# lm2731.net
KiCad netlist of a schematic drawn in Altium Designer
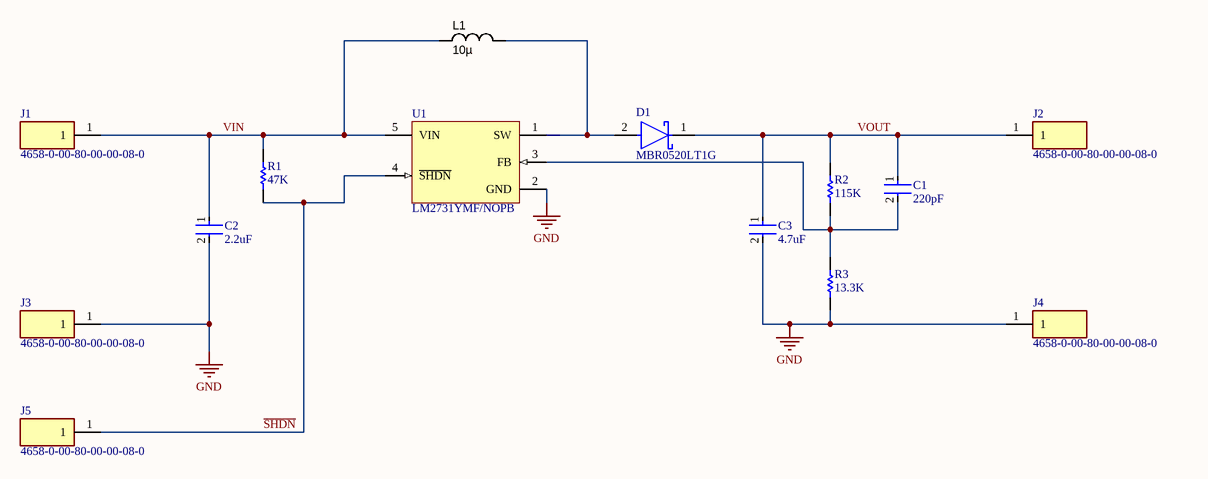
[diagram p0: lm2731.SchDoc]

(export (version "E")
  (design (tool "Eeschema 10.0.6"))
  (components
    (comp (ref "C1")
      (value "220pF")
      (footprint "FP-CL10-IPC_C")
      (description "Cap Ceramic 220pF 50V C0G ±5% Pad SMD 0603 +125°C T/R")
      (fields (field (name "VOLTAGE") "50V") (field (name "TOLERANCE") "5%"))
      (libsource (lib "Altium Content Vault") (part "b4654b650e69147ec39a6b967a45e02"))
    )
    (comp (ref "C2")
      (value "2.2uF")
      (footprint "FP-GRM188-0_2-IPC_C")
      (description "Chip Multilayer Ceramic Capacitors for General Purpose, 0603, 2.2uF, X5R, 15%, 10%, 50V")
      (fields (field (name "TOLERANCE") "10%"))
      (libsource (lib "Altium Content Vault") (part "11868f565c42a9108669ba33697ecf6"))
    )
    (comp (ref "C3")
      (value "4.7uF")
      (footprint "FP-GRM31C-0_2-e0_3_0_8-IPC_C")
      (description "Chip Multilayer Ceramic Capacitors for General Purpose, 1206, 4.7uF, X7R, 15%, 10%, 50V")
      (fields (field (name "VOLTAGE") "50V") (field (name "TOLERANCE") "10%"))
      (libsource (lib "Altium Content Vault") (part "02cd4be3c70576c341d710602a673aa"))
    )
    (comp (ref "D1")
      (value "MBR0520LT1G")
      (footprint "FP-425-04-IPC_C")
      (description "DIODE SCHOTTKY 20V 500MA SOD123")
      (libsource (lib "Altium Content Vault") (part "1d6ec82d83fb6aee721767c19dac4b9"))
    )
    (comp (ref "J1")
      (value "4658-0-00-80-00-00-08-0")
      (footprint "SamacSys:4658000800000080")
      (description "Connector")
      (fields (field (name "MOUSER PART NUMBER") "575-4658000800000080"))
      (libsource (lib "SamacSys") (part "4658-0-00-80-00-00-08-0"))
    )
    (comp (ref "J2")
      (value "4658-0-00-80-00-00-08-0")
      (footprint "4658000800000080")
      (description "Connector")
      (fields (field (name "MOUSER PART NUMBER") "575-4658000800000080"))
      (libsource (lib "") (part "4658-0-00-80-00-00-08-0_1"))
    )
    (comp (ref "J3")
      (value "4658-0-00-80-00-00-08-0")
      (footprint "4658000800000080")
      (description "Connector")
      (fields (field (name "MOUSER PART NUMBER") "575-4658000800000080"))
      (libsource (lib "SamacSys") (part "4658-0-00-80-00-00-08-0"))
    )
    (comp (ref "J4")
      (value "4658-0-00-80-00-00-08-0")
      (footprint "4658000800000080")
      (description "Connector")
      (fields (field (name "MOUSER PART NUMBER") "575-4658000800000080"))
      (libsource (lib "") (part "4658-0-00-80-00-00-08-0_1"))
    )
    (comp (ref "J5")
      (value "4658-0-00-80-00-00-08-0")
      (footprint "4658000800000080")
      (description "Connector")
      (fields (field (name "MOUSER PART NUMBER") "575-4658000800000080"))
      (libsource (lib "SamacSys") (part "4658-0-00-80-00-00-08-0"))
    )
    (comp (ref "L1")
      (value "10µ")
      (footprint "INDC3225X250N")
      (description "Inductor SMD Low DCR 10 µH 900mA 20% 1210")
      (fields (field (name "TOLERANCE") "±20%"))
      (libsource (lib "PBL - Inductors") (part "INDC_10u_LowRDC"))
    )
    (comp (ref "R1")
      (value "47K")
      (footprint "RESC1608X55X30ML15T15")
      (description "Chip Resistor, 47 KOhm, +/- 1%, 0.1 W, -55 to 155 degC, 0603 (1608 Metric), RoHS, Tape and Reel")
      (fields (field (name "MANUFACTURER PART NUMBER") "ERJ3EKF4702V"))
      (libsource (lib "Altium Content Vault") (part "RES-2"))
    )
    (comp (ref "R2")
      (value "115K")
      (footprint "RESC1608X55X30ML15T15")
      (fields (field (name "MANUFACTURER") "Panasonic") (field (name "PART NUMBER") "ERJ-3EKF1153V"))
      (libsource (lib "Altium Content Vault") (part "RES"))
    )
    (comp (ref "R3")
      (value "13.3K")
      (footprint "RESC1608X55X30LL15T15")
      (fields (field (name "MANUFACTURER") "Panasonic") (field (name "PART NUMBER") "ERJ-3EKF1332V"))
      (libsource (lib "Altium Content Vault") (part "RES"))
    )
    (comp (ref "U1")
      (value "LM2731YMF/NOPB")
      (footprint "DBV0005A_N")
      (description "0.6/1.6 MHz Boost Converters With 22V Internal FET Switch in 5-pin SOT-23, Pb-Free")
      (fields (field (name "MANUFACTURER") "Texas Instruments"))
      (libsource (lib "Altium Content Vault") (part "PM-REG-LM2731"))
    )
  )
  (nets
    (net (code "1") (name "/VIN") (class "Default")
      (node (ref "C2") (pin "1") (pinfunction "1_1") (pintype "passive"))
      (node (ref "J1") (pin "1") (pinfunction "1_1") (pintype "passive"))
      (node (ref "L1") (pin "1") (pinfunction "1_1") (pintype "passive"))
      (node (ref "R1") (pin "2") (pinfunction "2_2") (pintype "passive"))
      (node (ref "U1") (pin "5") (pinfunction "VIN_5") (pintype "power_in"))
    )
    (net (code "2") (name "/VOUT") (class "Default")
      (node (ref "C1") (pin "1") (pinfunction "1_1") (pintype "passive"))
      (node (ref "C3") (pin "1") (pinfunction "1_1") (pintype "passive"))
      (node (ref "D1") (pin "1") (pinfunction "C_1") (pintype "passive"))
      (node (ref "J2") (pin "1") (pinfunction "1_1") (pintype "passive"))
      (node (ref "R2") (pin "2") (pinfunction "2_2") (pintype "passive"))
    )
    (net (code "3") (name "/~{SHDN}") (class "Default")
      (node (ref "J5") (pin "1") (pinfunction "1_1") (pintype "passive"))
      (node (ref "R1") (pin "1") (pinfunction "1_1") (pintype "passive"))
      (node (ref "U1") (pin "4") (pinfunction "~{SHDN}_4") (pintype "input"))
    )
    (net (code "4") (name "GND") (class "Default")
      (node (ref "C2") (pin "2") (pinfunction "2_2") (pintype "passive"))
      (node (ref "C3") (pin "2") (pinfunction "2_2") (pintype "passive"))
      (node (ref "J3") (pin "1") (pinfunction "1_1") (pintype "passive"))
      (node (ref "J4") (pin "1") (pinfunction "1_1") (pintype "passive"))
      (node (ref "R3") (pin "1") (pinfunction "1_1") (pintype "passive"))
      (node (ref "U1") (pin "2") (pinfunction "GND_2") (pintype "power_in"))
    )
    (net (code "5") (name "Net-(D1-A)") (class "Default")
      (node (ref "D1") (pin "2") (pinfunction "A_2") (pintype "passive"))
      (node (ref "L1") (pin "2") (pinfunction "2_2") (pintype "passive"))
      (node (ref "U1") (pin "1") (pinfunction "SW_1") (pintype "power_in"))
    )
    (net (code "6") (name "Net-(U1-FB)") (class "Default")
      (node (ref "C1") (pin "2") (pinfunction "2_2") (pintype "passive"))
      (node (ref "R2") (pin "1") (pinfunction "1_1") (pintype "passive"))
      (node (ref "R3") (pin "2") (pinfunction "2_2") (pintype "passive"))
      (node (ref "U1") (pin "3") (pinfunction "FB_3") (pintype "input"))
    )
  )
)
